# ide-8bit.net
KiCad netlist of a schematic drawn in EAGLE
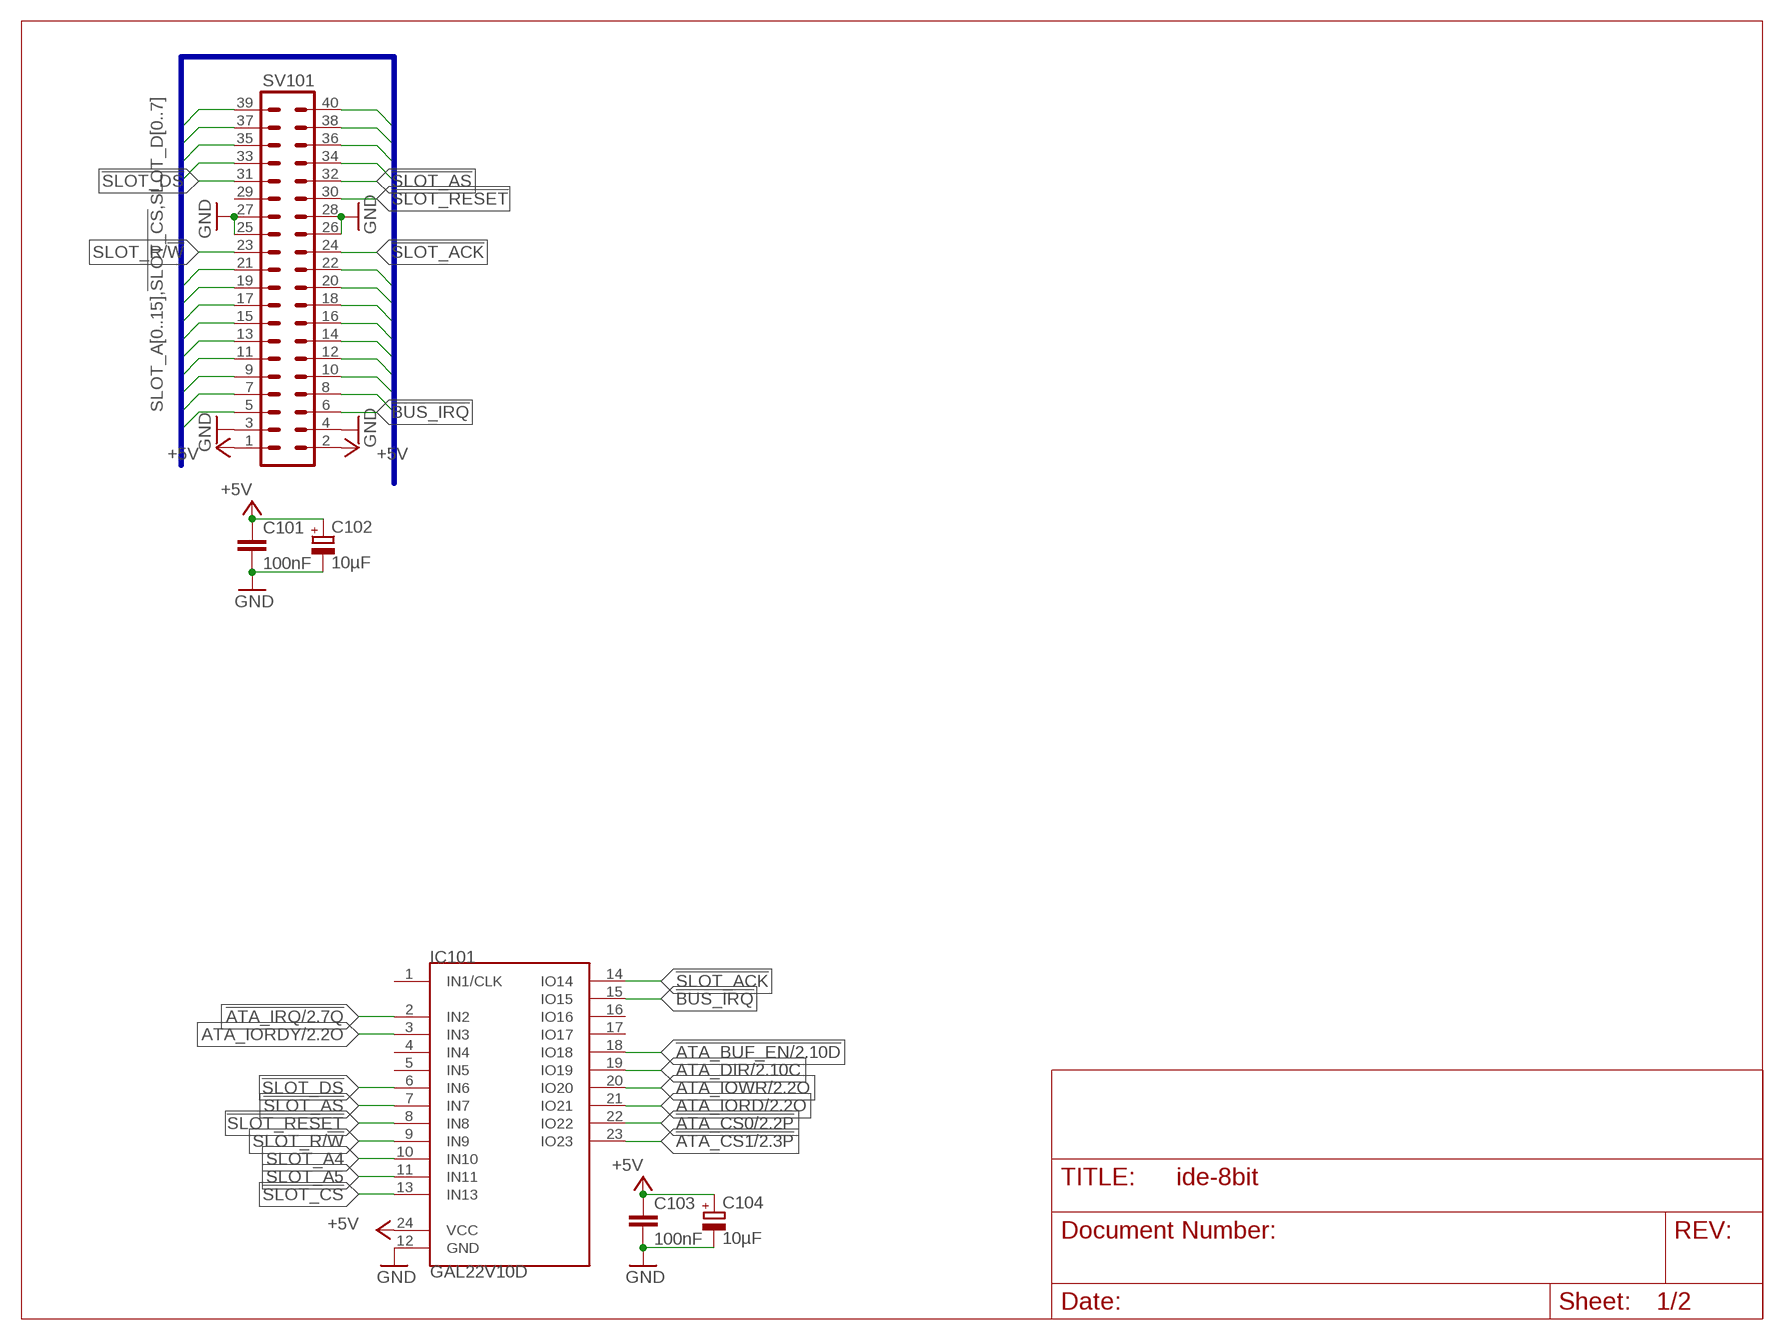
[diagram p0: schematic, sheet 1]
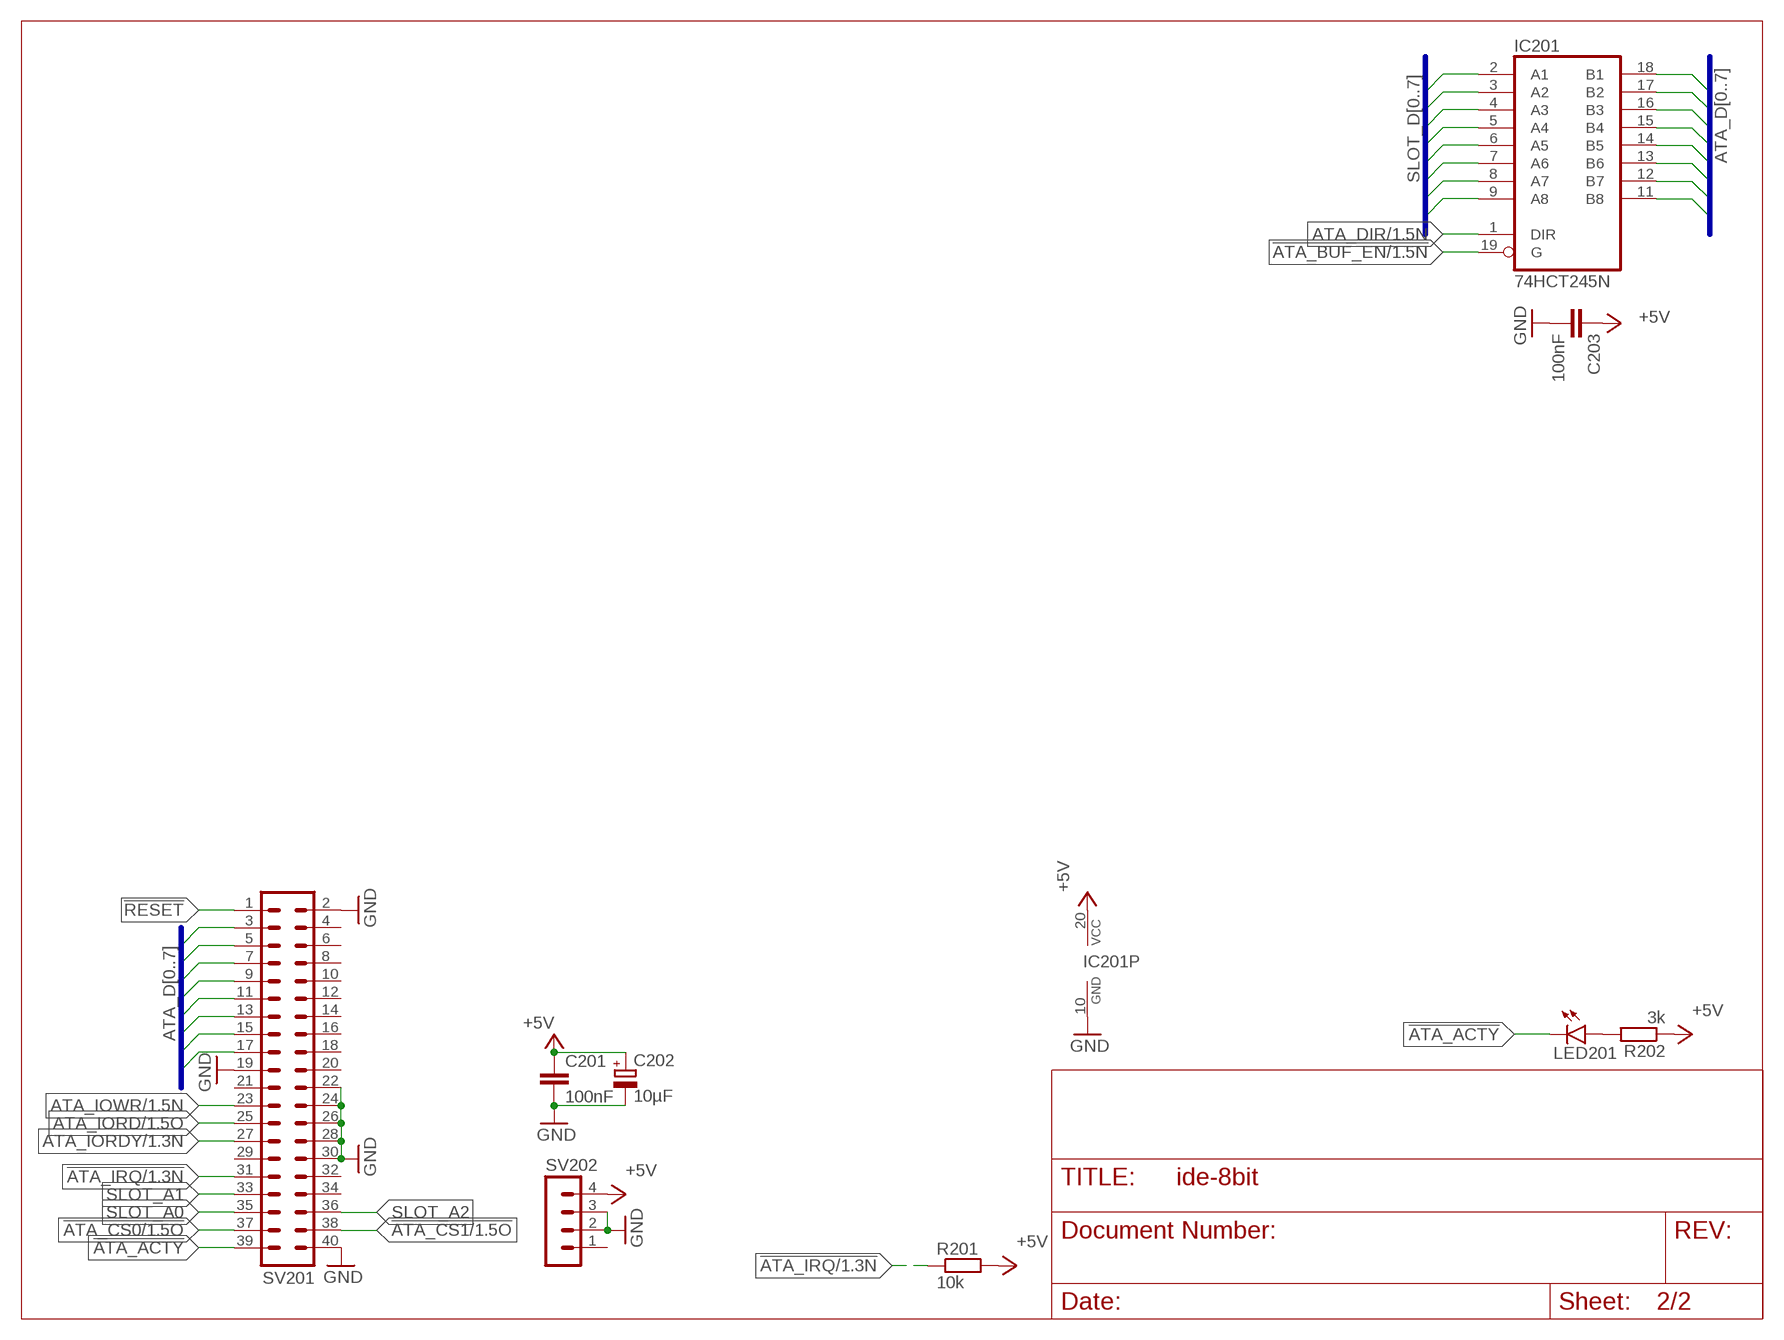
[diagram p1: schematic, sheet 2]

(export (version "E")
  (design (tool "Eeschema 10.0.6"))
  (components
    (comp (ref "C101")
      (value "100nF")
      (footprint "eagle-import:C0805")
      (libsource (lib "eagle-import") (part "C-EUC0805"))
    )
    (comp (ref "C102")
      (value "10µF")
      (footprint "eagle-import:SMC_B")
      (libsource (lib "eagle-import") (part "CPOL-EUSMCB"))
    )
    (comp (ref "C103")
      (value "100nF")
      (footprint "eagle-import:C0805")
      (libsource (lib "eagle-import") (part "C-EUC0805"))
    )
    (comp (ref "C104")
      (value "10µF")
      (footprint "eagle-import:SMC_B")
      (libsource (lib "eagle-import") (part "CPOL-EUSMCB"))
    )
    (comp (ref "IC101")
      (value "GAL22V10D")
      (footprint "eagle-import:DIL24S")
      (libsource (lib "eagle-import") (part "GAL22V10DIP24"))
    )
    (comp (ref "SV101")
      (value "MA20-2W")
      (footprint "eagle-import:MA20-2W")
      (libsource (lib "eagle-import") (part "MA20-2W"))
    )
    (comp (ref "C201")
      (value "100nF")
      (footprint "eagle-import:C0805")
      (libsource (lib "eagle-import") (part "C-EUC0805"))
    )
    (comp (ref "C202")
      (value "10µF")
      (footprint "eagle-import:SMC_B")
      (libsource (lib "eagle-import") (part "CPOL-EUSMCB"))
    )
    (comp (ref "C203")
      (value "100nF")
      (footprint "eagle-import:C0805")
      (libsource (lib "eagle-import") (part "C-EUC0805"))
    )
    (comp (ref "IC201")
      (value "74HCT245N")
      (footprint "eagle-import:DIL20")
      (fields (field (name "MOUSER") "595-SN74HCT245N") (field (name "MOUSER_SOCKET") "575-1104732041001000"))
      (libsource (lib "eagle-import") (part "74245NHCT"))
    )
    (comp (ref "LED201")
      (value "LEDCHIPLED_1206")
      (footprint "eagle-import:CHIPLED_1206")
      (libsource (lib "eagle-import") (part "LEDCHIPLED_1206"))
    )
    (comp (ref "R201")
      (value "10k")
      (footprint "eagle-import:R2012")
      (libsource (lib "eagle-import") (part "R-EU_R2012"))
    )
    (comp (ref "R202")
      (value "3k")
      (footprint "eagle-import:R2012")
      (libsource (lib "eagle-import") (part "R-EU_R2012"))
    )
    (comp (ref "SV201")
      (value "ML40L")
      (footprint "eagle-import:ML40L")
      (libsource (lib "eagle-import") (part "ML40L"))
    )
    (comp (ref "SV202")
      (value "MA04-1")
      (footprint "eagle-import:MA04-1")
      (libsource (lib "eagle-import") (part "MA04-1"))
    )
  )
  (nets
    (net (code "1") (name "+5V") (class "Default")
      (node (ref "C101") (pin "1") (pinfunction "1_1") (pintype "passive"))
      (node (ref "C102") (pin "+") (pinfunction "+_+") (pintype "passive"))
      (node (ref "C103") (pin "1") (pinfunction "1_1") (pintype "passive"))
      (node (ref "C104") (pin "+") (pinfunction "+_+") (pintype "passive"))
      (node (ref "C201") (pin "1") (pinfunction "1_1") (pintype "passive"))
      (node (ref "C202") (pin "+") (pinfunction "+_+") (pintype "passive"))
      (node (ref "C203") (pin "1") (pinfunction "1_1") (pintype "passive"))
      (node (ref "IC101") (pin "24") (pinfunction "VCC_24") (pintype "power_in"))
      (node (ref "IC201") (pin "20") (pinfunction "VCC_20") (pintype "power_in"))
      (node (ref "R201") (pin "2") (pinfunction "2_2") (pintype "passive"))
      (node (ref "R202") (pin "1") (pinfunction "1_1") (pintype "passive"))
      (node (ref "SV101") (pin "1") (pinfunction "1_1") (pintype "passive"))
      (node (ref "SV101") (pin "2") (pinfunction "2_2") (pintype "passive"))
      (node (ref "SV202") (pin "4") (pinfunction "4_4") (pintype "passive"))
    )
    (net (code "5") (name "ATA_D0") (class "Default")
      (node (ref "IC201") (pin "18") (pinfunction "B1_18") (pintype "bidirectional"))
      (node (ref "SV201") (pin "17") (pinfunction "17_17") (pintype "passive"))
    )
    (net (code "6") (name "ATA_D1") (class "Default")
      (node (ref "IC201") (pin "17") (pinfunction "B2_17") (pintype "bidirectional"))
      (node (ref "SV201") (pin "15") (pinfunction "15_15") (pintype "passive"))
    )
    (net (code "7") (name "ATA_D2") (class "Default")
      (node (ref "IC201") (pin "16") (pinfunction "B3_16") (pintype "bidirectional"))
      (node (ref "SV201") (pin "13") (pinfunction "13_13") (pintype "passive"))
    )
    (net (code "8") (name "ATA_D3") (class "Default")
      (node (ref "IC201") (pin "15") (pinfunction "B4_15") (pintype "bidirectional"))
      (node (ref "SV201") (pin "11") (pinfunction "11_11") (pintype "passive"))
    )
    (net (code "9") (name "ATA_D4") (class "Default")
      (node (ref "IC201") (pin "14") (pinfunction "B5_14") (pintype "bidirectional"))
      (node (ref "SV201") (pin "9") (pinfunction "9_9") (pintype "passive"))
    )
    (net (code "10") (name "ATA_D5") (class "Default")
      (node (ref "IC201") (pin "13") (pinfunction "B6_13") (pintype "bidirectional"))
      (node (ref "SV201") (pin "7") (pinfunction "7_7") (pintype "passive"))
    )
    (net (code "11") (name "ATA_D6") (class "Default")
      (node (ref "IC201") (pin "12") (pinfunction "B7_12") (pintype "bidirectional"))
      (node (ref "SV201") (pin "5") (pinfunction "5_5") (pintype "passive"))
    )
    (net (code "12") (name "ATA_D7") (class "Default")
      (node (ref "IC201") (pin "11") (pinfunction "B8_11") (pintype "bidirectional"))
      (node (ref "SV201") (pin "3") (pinfunction "3_3") (pintype "passive"))
    )
    (net (code "13") (name "ATA_DIR") (class "Default")
      (node (ref "IC101") (pin "19") (pinfunction "IO19_19") (pintype "bidirectional"))
      (node (ref "IC201") (pin "1") (pinfunction "DIR_1") (pintype "input"))
    )
    (net (code "14") (name "ATA_IORD") (class "Default")
      (node (ref "IC101") (pin "21") (pinfunction "IO21_21") (pintype "bidirectional"))
      (node (ref "SV201") (pin "25") (pinfunction "25_25") (pintype "passive"))
    )
    (net (code "15") (name "ATA_IORDY") (class "Default")
      (node (ref "IC101") (pin "3") (pinfunction "IN3_3") (pintype "input"))
      (node (ref "SV201") (pin "27") (pinfunction "27_27") (pintype "passive"))
    )
    (net (code "16") (name "ATA_IOWR") (class "Default")
      (node (ref "IC101") (pin "20") (pinfunction "IO20_20") (pintype "bidirectional"))
      (node (ref "SV201") (pin "23") (pinfunction "23_23") (pintype "passive"))
    )
    (net (code "17") (name "GND") (class "Default")
      (node (ref "C101") (pin "2") (pinfunction "2_2") (pintype "passive"))
      (node (ref "C102") (pin "-") (pinfunction "-_-") (pintype "passive"))
      (node (ref "C103") (pin "2") (pinfunction "2_2") (pintype "passive"))
      (node (ref "C104") (pin "-") (pinfunction "-_-") (pintype "passive"))
      (node (ref "C201") (pin "2") (pinfunction "2_2") (pintype "passive"))
      (node (ref "C202") (pin "-") (pinfunction "-_-") (pintype "passive"))
      (node (ref "C203") (pin "2") (pinfunction "2_2") (pintype "passive"))
      (node (ref "IC101") (pin "12") (pinfunction "GND_12") (pintype "power_in"))
      (node (ref "IC201") (pin "10") (pinfunction "GND_10") (pintype "power_in"))
      (node (ref "SV101") (pin "25") (pinfunction "25_25") (pintype "passive"))
      (node (ref "SV101") (pin "26") (pinfunction "26_26") (pintype "passive"))
      (node (ref "SV101") (pin "27") (pinfunction "27_27") (pintype "passive"))
      (node (ref "SV101") (pin "28") (pinfunction "28_28") (pintype "passive"))
      (node (ref "SV101") (pin "3") (pinfunction "3_3") (pintype "passive"))
      (node (ref "SV101") (pin "4") (pinfunction "4_4") (pintype "passive"))
      (node (ref "SV201") (pin "19") (pinfunction "19_19") (pintype "passive"))
      (node (ref "SV201") (pin "2") (pinfunction "2_2") (pintype "passive"))
      (node (ref "SV201") (pin "22") (pinfunction "22_22") (pintype "passive"))
      (node (ref "SV201") (pin "24") (pinfunction "24_24") (pintype "passive"))
      (node (ref "SV201") (pin "26") (pinfunction "26_26") (pintype "passive"))
      (node (ref "SV201") (pin "28") (pinfunction "28_28") (pintype "passive"))
      (node (ref "SV201") (pin "30") (pinfunction "30_30") (pintype "passive"))
      (node (ref "SV201") (pin "40") (pinfunction "40_40") (pintype "passive"))
      (node (ref "SV202") (pin "2") (pinfunction "2_2") (pintype "passive"))
      (node (ref "SV202") (pin "3") (pinfunction "3_3") (pintype "passive"))
    )
    (net (code "18") (name "Net-(LED201-PadA)") (class "Default")
      (node (ref "LED201") (pin "A") (pinfunction "A_A") (pintype "passive"))
      (node (ref "R202") (pin "2") (pinfunction "2_2") (pintype "passive"))
    )
    (net (code "19") (name "SLOT_A0") (class "Default")
      (node (ref "SV101") (pin "12") (pinfunction "12_12") (pintype "passive"))
      (node (ref "SV201") (pin "35") (pinfunction "35_35") (pintype "passive"))
    )
    (net (code "20") (name "SLOT_A1") (class "Default")
      (node (ref "SV101") (pin "10") (pinfunction "10_10") (pintype "passive"))
      (node (ref "SV201") (pin "33") (pinfunction "33_33") (pintype "passive"))
    )
    (net (code "21") (name "SLOT_A2") (class "Default")
      (node (ref "SV101") (pin "8") (pinfunction "8_8") (pintype "passive"))
      (node (ref "SV201") (pin "36") (pinfunction "36_36") (pintype "passive"))
    )
    (net (code "22") (name "SLOT_A4") (class "Default")
      (node (ref "IC101") (pin "10") (pinfunction "IN10_10") (pintype "input"))
      (node (ref "SV101") (pin "9") (pinfunction "9_9") (pintype "passive"))
    )
    (net (code "23") (name "SLOT_A5") (class "Default")
      (node (ref "IC101") (pin "11") (pinfunction "IN11_11") (pintype "input"))
      (node (ref "SV101") (pin "11") (pinfunction "11_11") (pintype "passive"))
    )
    (net (code "24") (name "SLOT_D0") (class "Default")
      (node (ref "IC201") (pin "2") (pinfunction "A1_2") (pintype "bidirectional"))
      (node (ref "SV101") (pin "35") (pinfunction "35_35") (pintype "passive"))
    )
    (net (code "25") (name "SLOT_D1") (class "Default")
      (node (ref "IC201") (pin "3") (pinfunction "A2_3") (pintype "bidirectional"))
      (node (ref "SV101") (pin "37") (pinfunction "37_37") (pintype "passive"))
    )
    (net (code "26") (name "SLOT_D2") (class "Default")
      (node (ref "IC201") (pin "4") (pinfunction "A3_4") (pintype "bidirectional"))
      (node (ref "SV101") (pin "39") (pinfunction "39_39") (pintype "passive"))
    )
    (net (code "27") (name "SLOT_D3") (class "Default")
      (node (ref "IC201") (pin "5") (pinfunction "A4_5") (pintype "bidirectional"))
      (node (ref "SV101") (pin "40") (pinfunction "40_40") (pintype "passive"))
    )
    (net (code "28") (name "SLOT_D4") (class "Default")
      (node (ref "IC201") (pin "6") (pinfunction "A5_6") (pintype "bidirectional"))
      (node (ref "SV101") (pin "38") (pinfunction "38_38") (pintype "passive"))
    )
    (net (code "29") (name "SLOT_D5") (class "Default")
      (node (ref "IC201") (pin "7") (pinfunction "A6_7") (pintype "bidirectional"))
      (node (ref "SV101") (pin "36") (pinfunction "36_36") (pintype "passive"))
    )
    (net (code "30") (name "SLOT_D6") (class "Default")
      (node (ref "IC201") (pin "8") (pinfunction "A7_8") (pintype "bidirectional"))
      (node (ref "SV101") (pin "34") (pinfunction "34_34") (pintype "passive"))
    )
    (net (code "31") (name "SLOT_D7") (class "Default")
      (node (ref "IC201") (pin "9") (pinfunction "A8_9") (pintype "bidirectional"))
      (node (ref "SV101") (pin "33") (pinfunction "33_33") (pintype "passive"))
    )
    (net (code "32") (name "SLOT_R{slash}~{W}") (class "Default")
      (node (ref "IC101") (pin "9") (pinfunction "IN9_9") (pintype "input"))
      (node (ref "SV101") (pin "23") (pinfunction "23_23") (pintype "passive"))
    )
    (net (code "33") (name "unconnected-(IC101-IN1{slash}CLK-Pad1)") (class "Default")
      (node (ref "IC101") (pin "1") (pinfunction "IN1/CLK_1") (pintype "input"))
    )
    (net (code "34") (name "unconnected-(IC101-IN4-Pad4)") (class "Default")
      (node (ref "IC101") (pin "4") (pinfunction "IN4_4") (pintype "input"))
    )
    (net (code "35") (name "unconnected-(IC101-IN5-Pad5)") (class "Default")
      (node (ref "IC101") (pin "5") (pinfunction "IN5_5") (pintype "input"))
    )
    (net (code "36") (name "unconnected-(IC101-IO16-Pad16)") (class "Default")
      (node (ref "IC101") (pin "16") (pinfunction "IO16_16") (pintype "bidirectional"))
    )
    (net (code "37") (name "unconnected-(IC101-IO17-Pad17)") (class "Default")
      (node (ref "IC101") (pin "17") (pinfunction "IO17_17") (pintype "bidirectional"))
    )
    (net (code "38") (name "unconnected-(SV101-Pad7)") (class "Default")
      (node (ref "SV101") (pin "7") (pinfunction "7_7") (pintype "passive"))
    )
    (net (code "39") (name "unconnected-(SV101-Pad13)") (class "Default")
      (node (ref "SV101") (pin "13") (pinfunction "13_13") (pintype "passive"))
    )
    (net (code "40") (name "unconnected-(SV101-Pad14)") (class "Default")
      (node (ref "SV101") (pin "14") (pinfunction "14_14") (pintype "passive"))
    )
    (net (code "41") (name "unconnected-(SV101-Pad15)") (class "Default")
      (node (ref "SV101") (pin "15") (pinfunction "15_15") (pintype "passive"))
    )
    (net (code "42") (name "unconnected-(SV101-Pad16)") (class "Default")
      (node (ref "SV101") (pin "16") (pinfunction "16_16") (pintype "passive"))
    )
    (net (code "43") (name "unconnected-(SV101-Pad17)") (class "Default")
      (node (ref "SV101") (pin "17") (pinfunction "17_17") (pintype "passive"))
    )
    (net (code "44") (name "unconnected-(SV101-Pad18)") (class "Default")
      (node (ref "SV101") (pin "18") (pinfunction "18_18") (pintype "passive"))
    )
    (net (code "45") (name "unconnected-(SV101-Pad19)") (class "Default")
      (node (ref "SV101") (pin "19") (pinfunction "19_19") (pintype "passive"))
    )
    (net (code "46") (name "unconnected-(SV101-Pad20)") (class "Default")
      (node (ref "SV101") (pin "20") (pinfunction "20_20") (pintype "passive"))
    )
    (net (code "47") (name "unconnected-(SV101-Pad21)") (class "Default")
      (node (ref "SV101") (pin "21") (pinfunction "21_21") (pintype "passive"))
    )
    (net (code "48") (name "unconnected-(SV101-Pad22)") (class "Default")
      (node (ref "SV101") (pin "22") (pinfunction "22_22") (pintype "passive"))
    )
    (net (code "49") (name "unconnected-(SV101-Pad29)") (class "Default")
      (node (ref "SV101") (pin "29") (pinfunction "29_29") (pintype "passive"))
    )
    (net (code "50") (name "unconnected-(SV201-Pad4)") (class "Default")
      (node (ref "SV201") (pin "4") (pinfunction "4_4") (pintype "passive"))
    )
    (net (code "51") (name "unconnected-(SV201-Pad6)") (class "Default")
      (node (ref "SV201") (pin "6") (pinfunction "6_6") (pintype "passive"))
    )
    (net (code "52") (name "unconnected-(SV201-Pad8)") (class "Default")
      (node (ref "SV201") (pin "8") (pinfunction "8_8") (pintype "passive"))
    )
    (net (code "53") (name "unconnected-(SV201-Pad10)") (class "Default")
      (node (ref "SV201") (pin "10") (pinfunction "10_10") (pintype "passive"))
    )
    (net (code "54") (name "unconnected-(SV201-Pad12)") (class "Default")
      (node (ref "SV201") (pin "12") (pinfunction "12_12") (pintype "passive"))
    )
    (net (code "55") (name "unconnected-(SV201-Pad14)") (class "Default")
      (node (ref "SV201") (pin "14") (pinfunction "14_14") (pintype "passive"))
    )
    (net (code "56") (name "unconnected-(SV201-Pad16)") (class "Default")
      (node (ref "SV201") (pin "16") (pinfunction "16_16") (pintype "passive"))
    )
    (net (code "57") (name "unconnected-(SV201-Pad18)") (class "Default")
      (node (ref "SV201") (pin "18") (pinfunction "18_18") (pintype "passive"))
    )
    (net (code "58") (name "unconnected-(SV201-Pad20)") (class "Default")
      (node (ref "SV201") (pin "20") (pinfunction "20_20") (pintype "passive"))
    )
    (net (code "59") (name "unconnected-(SV201-Pad21)") (class "Default")
      (node (ref "SV201") (pin "21") (pinfunction "21_21") (pintype "passive"))
    )
    (net (code "60") (name "unconnected-(SV201-Pad29)") (class "Default")
      (node (ref "SV201") (pin "29") (pinfunction "29_29") (pintype "passive"))
    )
    (net (code "61") (name "unconnected-(SV201-Pad32)") (class "Default")
      (node (ref "SV201") (pin "32") (pinfunction "32_32") (pintype "passive"))
    )
    (net (code "62") (name "unconnected-(SV201-Pad34)") (class "Default")
      (node (ref "SV201") (pin "34") (pinfunction "34_34") (pintype "passive"))
    )
    (net (code "63") (name "unconnected-(SV202-Pad1)") (class "Default")
      (node (ref "SV202") (pin "1") (pinfunction "1_1") (pintype "passive"))
    )
    (net (code "64") (name "~{ATA_ACTY}") (class "Default")
      (node (ref "LED201") (pin "C") (pinfunction "C_C") (pintype "passive"))
      (node (ref "SV201") (pin "39") (pinfunction "39_39") (pintype "passive"))
    )
    (net (code "65") (name "~{ATA_BUF_EN}") (class "Default")
      (node (ref "IC101") (pin "18") (pinfunction "IO18_18") (pintype "bidirectional"))
      (node (ref "IC201") (pin "19") (pinfunction "G_19") (pintype "input"))
    )
    (net (code "66") (name "~{ATA_CS0}") (class "Default")
      (node (ref "IC101") (pin "22") (pinfunction "IO22_22") (pintype "bidirectional"))
      (node (ref "SV201") (pin "37") (pinfunction "37_37") (pintype "passive"))
    )
    (net (code "67") (name "~{ATA_CS1}") (class "Default")
      (node (ref "IC101") (pin "23") (pinfunction "IO23_23") (pintype "bidirectional"))
      (node (ref "SV201") (pin "38") (pinfunction "38_38") (pintype "passive"))
    )
    (net (code "68") (name "~{ATA_IRQ}") (class "Default")
      (node (ref "IC101") (pin "2") (pinfunction "IN2_2") (pintype "input"))
      (node (ref "R201") (pin "1") (pinfunction "1_1") (pintype "passive"))
      (node (ref "SV201") (pin "31") (pinfunction "31_31") (pintype "passive"))
    )
    (net (code "69") (name "~{BUS_IRQ}") (class "Default")
      (node (ref "IC101") (pin "15") (pinfunction "IO15_15") (pintype "bidirectional"))
      (node (ref "SV101") (pin "6") (pinfunction "6_6") (pintype "passive"))
    )
    (net (code "70") (name "~{RESET}") (class "Default")
      (node (ref "SV201") (pin "1") (pinfunction "1_1") (pintype "passive"))
    )
    (net (code "71") (name "~{SLOT_ACK}") (class "Default")
      (node (ref "IC101") (pin "14") (pinfunction "IO14_14") (pintype "bidirectional"))
      (node (ref "SV101") (pin "24") (pinfunction "24_24") (pintype "passive"))
    )
    (net (code "72") (name "~{SLOT_AS}") (class "Default")
      (node (ref "IC101") (pin "7") (pinfunction "IN7_7") (pintype "input"))
      (node (ref "SV101") (pin "32") (pinfunction "32_32") (pintype "passive"))
    )
    (net (code "73") (name "~{SLOT_CS}") (class "Default")
      (node (ref "IC101") (pin "13") (pinfunction "IN13_13") (pintype "input"))
      (node (ref "SV101") (pin "5") (pinfunction "5_5") (pintype "passive"))
    )
    (net (code "74") (name "~{SLOT_DS}") (class "Default")
      (node (ref "IC101") (pin "6") (pinfunction "IN6_6") (pintype "input"))
      (node (ref "SV101") (pin "31") (pinfunction "31_31") (pintype "passive"))
    )
    (net (code "75") (name "~{SLOT_RESET}") (class "Default")
      (node (ref "IC101") (pin "8") (pinfunction "IN8_8") (pintype "input"))
      (node (ref "SV101") (pin "30") (pinfunction "30_30") (pintype "passive"))
    )
  )
)
